# reg_MIC29752.net
KiCad netlist of a schematic drawn in EAGLE
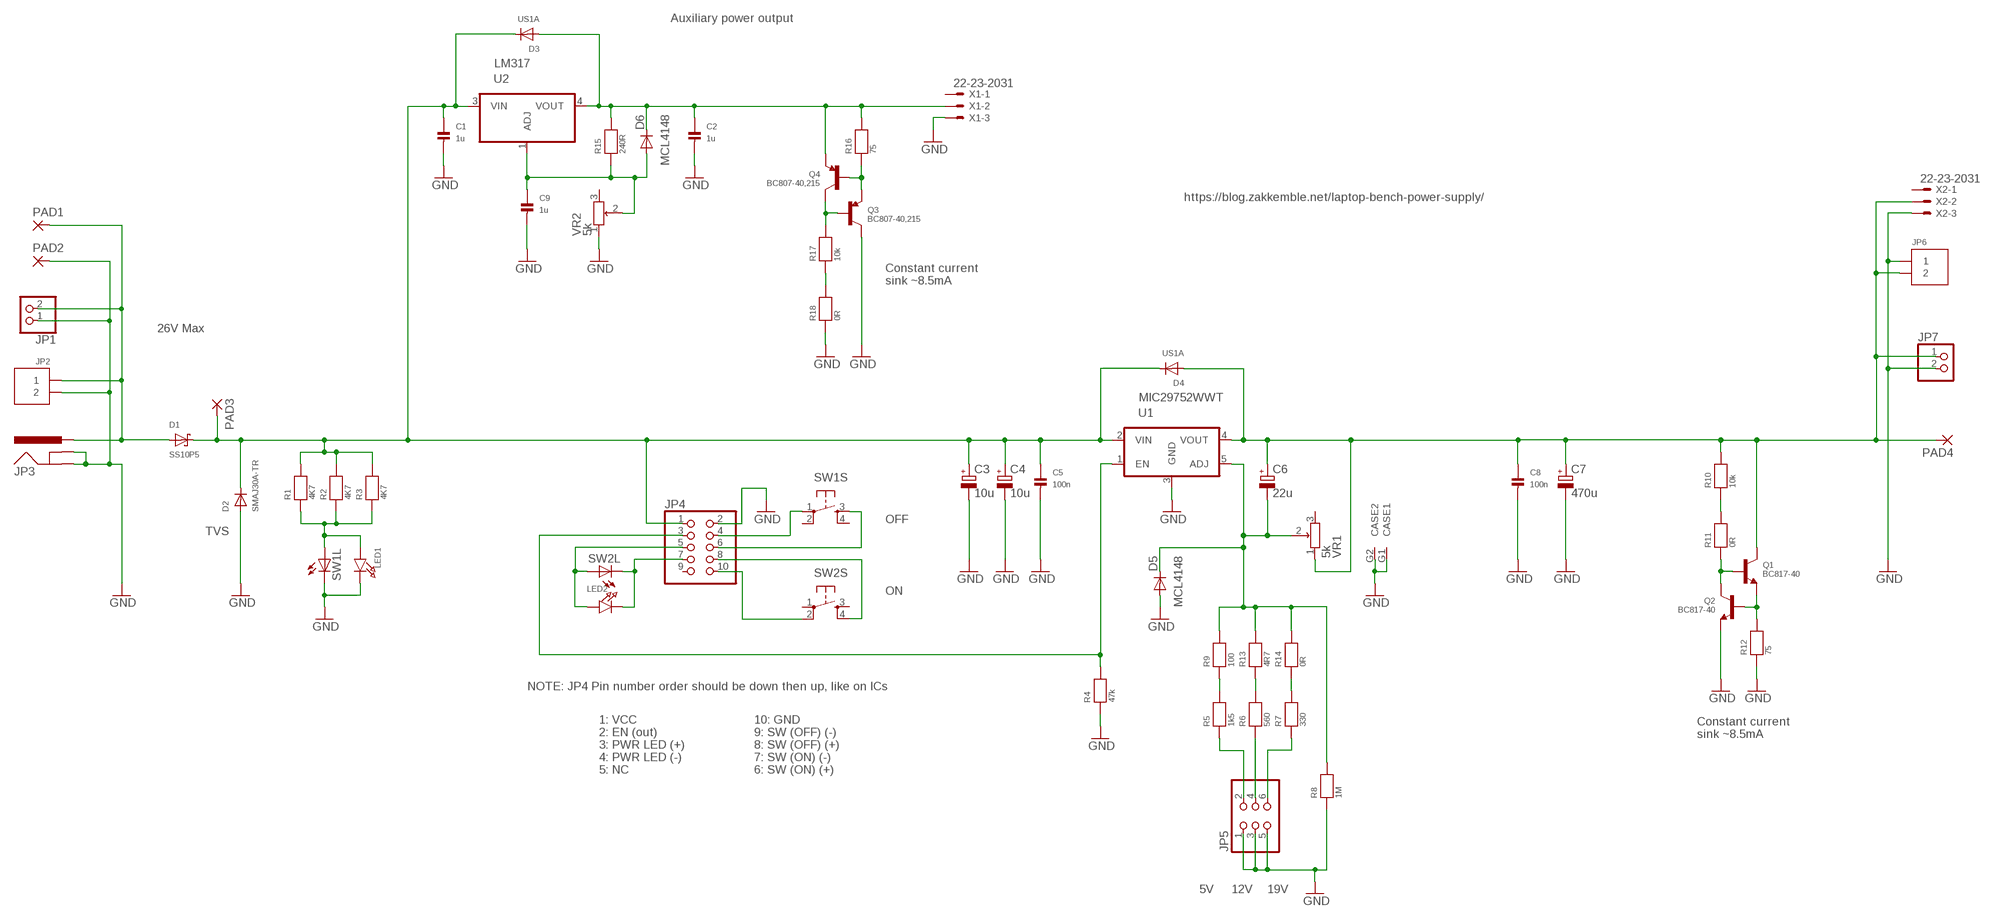
[diagram p0: schematic, sheet 1]

(export (version "E")
  (design (tool "Eeschema 10.0.6"))
  (components
    (comp (ref "C1")
      (value "1u")
      (footprint "eagle-import:0805_NO_OUTLINE")
      (libsource (lib "eagle-import") (part "zak_CAP_CERAMIC0805"))
    )
    (comp (ref "C2")
      (value "1u")
      (footprint "eagle-import:0805_NO_OUTLINE")
      (libsource (lib "eagle-import") (part "zak_CAP_CERAMIC0805"))
    )
    (comp (ref "C3")
      (value "10u")
      (footprint "eagle-import:E2-5")
      (libsource (lib "eagle-import") (part "CPOL-EUE2-5"))
    )
    (comp (ref "C4")
      (value "10u")
      (footprint "eagle-import:E2-5")
      (libsource (lib "eagle-import") (part "CPOL-EUE2-5"))
    )
    (comp (ref "C5")
      (value "100n")
      (footprint "eagle-import:_0603MP")
      (libsource (lib "eagle-import") (part "CAP_CERAMIC_0603MP"))
    )
    (comp (ref "C6")
      (value "22u")
      (footprint "eagle-import:E2-4")
      (libsource (lib "eagle-import") (part "CPOL-EUE2-4"))
    )
    (comp (ref "C7")
      (value "470u")
      (footprint "eagle-import:E5-10,5")
      (libsource (lib "eagle-import") (part "CPOL-EUE5-10.5"))
    )
    (comp (ref "C8")
      (value "100n")
      (footprint "eagle-import:_0603MP")
      (libsource (lib "eagle-import") (part "CAP_CERAMIC_0603MP"))
    )
    (comp (ref "C9")
      (value "1u")
      (footprint "eagle-import:0805_NO_OUTLINE")
      (libsource (lib "eagle-import") (part "zak_CAP_CERAMIC0805"))
    )
    (comp (ref "D1")
      (value "SS10P5")
      (footprint "eagle-import:TO-277A")
      (libsource (lib "eagle-import") (part "DIODE-SCHOTTKYTO-277A"))
    )
    (comp (ref "D2")
      (value "SMAJ30A-TR")
      (footprint "eagle-import:SMADIODE")
      (libsource (lib "eagle-import") (part "DIODESMA"))
    )
    (comp (ref "D3")
      (value "US1A")
      (footprint "eagle-import:SMADIODE")
      (libsource (lib "eagle-import") (part "DIODESMA"))
    )
    (comp (ref "D4")
      (value "US1A")
      (footprint "eagle-import:SMADIODE")
      (libsource (lib "eagle-import") (part "DIODESMA"))
    )
    (comp (ref "D5")
      (value "MCL4148")
      (footprint "eagle-import:MICROMELF-R")
      (libsource (lib "eagle-import") (part "DIODE-MICROMELF-R"))
    )
    (comp (ref "D6")
      (value "MCL4148")
      (footprint "eagle-import:MICROMELF-R")
      (libsource (lib "eagle-import") (part "DIODE-MICROMELF-R"))
    )
    (comp (ref "JP1")
      (value "PINHD-1X2")
      (footprint "eagle-import:1X02")
      (libsource (lib "eagle-import") (part "PINHD-1X2"))
    )
    (comp (ref "JP2")
      (value "TERM_BLOCK_2WAY")
      (footprint "eagle-import:TERM_2WAY")
      (libsource (lib "eagle-import") (part "TERM_BLOCK_2WAY"))
    )
    (comp (ref "JP3")
      (value "POWER_JACKPTH_HIGHCURRENT")
      (footprint "eagle-import:POWER_JACK_PTH_HIGHCURRENT")
      (libsource (lib "eagle-import") (part "POWER_JACKPTH_HIGHCURRENT"))
    )
    (comp (ref "JP4")
      (value "PINHD-2X5")
      (footprint "eagle-import:2X05")
      (libsource (lib "eagle-import") (part "PINHD-2X5"))
    )
    (comp (ref "JP5")
      (value "PINHD-2X3")
      (footprint "eagle-import:2X03")
      (libsource (lib "eagle-import") (part "PINHD-2X3"))
    )
    (comp (ref "JP6")
      (value "TERM_BLOCK_2WAY")
      (footprint "eagle-import:TERM_2WAY")
      (libsource (lib "eagle-import") (part "TERM_BLOCK_2WAY"))
    )
    (comp (ref "JP7")
      (value "PINHD-1X2")
      (footprint "eagle-import:1X02")
      (libsource (lib "eagle-import") (part "PINHD-1X2"))
    )
    (comp (ref "LED1")
      (value "LED0603_NOOUTLINE")
      (footprint "eagle-import:CHIPLED_0603_NOOUTLINE")
      (libsource (lib "eagle-import") (part "LED0603_NOOUTLINE"))
    )
    (comp (ref "LED2")
      (value "LED0603_NOOUTLINE")
      (footprint "eagle-import:CHIPLED_0603_NOOUTLINE")
      (libsource (lib "eagle-import") (part "LED0603_NOOUTLINE"))
    )
    (comp (ref "PAD1")
      (value "WIREPAD-3.81,2SCREW-3MM")
      (footprint "eagle-import:SCREWPAD-3MM")
      (libsource (lib "eagle-import") (part "WIREPAD-3.81,2SCREW-3MM"))
    )
    (comp (ref "PAD2")
      (value "WIREPAD-3.81,2SCREW-3MM")
      (footprint "eagle-import:SCREWPAD-3MM")
      (libsource (lib "eagle-import") (part "WIREPAD-3.81,2SCREW-3MM"))
    )
    (comp (ref "PAD3")
      (value "WIREPAD-3.81,2SCREW-3MM")
      (footprint "eagle-import:SCREWPAD-3MM")
      (libsource (lib "eagle-import") (part "WIREPAD-3.81,2SCREW-3MM"))
    )
    (comp (ref "PAD4")
      (value "WIREPAD-3.81,2SCREW-3MM")
      (footprint "eagle-import:SCREWPAD-3MM")
      (libsource (lib "eagle-import") (part "WIREPAD-3.81,2SCREW-3MM"))
    )
    (comp (ref "Q1")
      (value "BC817-40")
      (footprint "eagle-import:SOT23-W")
      (libsource (lib "eagle-import") (part "TRANSISTOR_NPNWAVE"))
    )
    (comp (ref "Q2")
      (value "BC817-40")
      (footprint "eagle-import:SOT23-WIDE")
      (libsource (lib "eagle-import") (part "TRANSISTOR_NPNWIDE"))
    )
    (comp (ref "Q3")
      (value "BC807-40,215")
      (footprint "eagle-import:SOT23-W")
      (libsource (lib "eagle-import") (part "TRANSISTOR_PNPSOT23-WAVE"))
    )
    (comp (ref "Q4")
      (value "BC807-40,215")
      (footprint "eagle-import:SOT23-WIDE")
      (libsource (lib "eagle-import") (part "TRANSISTOR_PNPWIDE"))
    )
    (comp (ref "R1")
      (value "4K7")
      (footprint "eagle-import:0402")
      (libsource (lib "eagle-import") (part "RESISTOR0402"))
    )
    (comp (ref "R2")
      (value "4K7")
      (footprint "eagle-import:0402")
      (libsource (lib "eagle-import") (part "RESISTOR0402"))
    )
    (comp (ref "R3")
      (value "4K7")
      (footprint "eagle-import:0402")
      (libsource (lib "eagle-import") (part "RESISTOR0402"))
    )
    (comp (ref "R4")
      (value "47k")
      (footprint "eagle-import:0402")
      (libsource (lib "eagle-import") (part "RESISTOR0402"))
    )
    (comp (ref "R5")
      (value "1k5")
      (footprint "eagle-import:0402")
      (libsource (lib "eagle-import") (part "RESISTOR0402"))
    )
    (comp (ref "R6")
      (value "560")
      (footprint "eagle-import:0402")
      (libsource (lib "eagle-import") (part "RESISTOR0402"))
    )
    (comp (ref "R7")
      (value "330")
      (footprint "eagle-import:0402")
      (libsource (lib "eagle-import") (part "RESISTOR0402"))
    )
    (comp (ref "R8")
      (value "1M")
      (footprint "eagle-import:0402")
      (libsource (lib "eagle-import") (part "RESISTOR0402"))
    )
    (comp (ref "R9")
      (value "100")
      (footprint "eagle-import:0402")
      (libsource (lib "eagle-import") (part "RESISTOR0402"))
    )
    (comp (ref "R10")
      (value "10k")
      (footprint "eagle-import:0402")
      (libsource (lib "eagle-import") (part "RESISTOR0402"))
    )
    (comp (ref "R11")
      (value "0R")
      (footprint "eagle-import:0402")
      (libsource (lib "eagle-import") (part "RESISTOR0402"))
    )
    (comp (ref "R12")
      (value "75")
      (footprint "eagle-import:0402")
      (libsource (lib "eagle-import") (part "RESISTOR0402"))
    )
    (comp (ref "R13")
      (value "4R7")
      (footprint "eagle-import:0402")
      (libsource (lib "eagle-import") (part "RESISTOR0402"))
    )
    (comp (ref "R14")
      (value "0R")
      (footprint "eagle-import:0402")
      (libsource (lib "eagle-import") (part "RESISTOR0402"))
    )
    (comp (ref "R15")
      (value "240R")
      (footprint "eagle-import:0402")
      (libsource (lib "eagle-import") (part "RESISTOR0402"))
    )
    (comp (ref "R16")
      (value "75")
      (footprint "eagle-import:0402")
      (libsource (lib "eagle-import") (part "RESISTOR0402"))
    )
    (comp (ref "R17")
      (value "10k")
      (footprint "eagle-import:0402")
      (libsource (lib "eagle-import") (part "RESISTOR0402"))
    )
    (comp (ref "R18")
      (value "0R")
      (footprint "eagle-import:0402")
      (libsource (lib "eagle-import") (part "RESISTOR0402"))
    )
    (comp (ref "SW1")
      (value "SPST_TACT_LED12MM_TH")
      (footprint "eagle-import:TACT_TH_12MM_LED")
      (libsource (lib "eagle-import") (part "SPST_TACT_LED12MM_TH"))
    )
    (comp (ref "SW2")
      (value "SPST_TACT_LED12MM_TH")
      (footprint "eagle-import:TACT_TH_12MM_LED")
      (libsource (lib "eagle-import") (part "SPST_TACT_LED12MM_TH"))
    )
    (comp (ref "U1")
      (value "MIC29752WWT")
      (footprint "eagle-import:TO247-5-REVERSE")
      (libsource (lib "eagle-import") (part "REGULATOR_3_ADJ_ENTO247-5-REVERSE"))
    )
    (comp (ref "U2")
      (value "LM317")
      (footprint "eagle-import:DPAK")
      (libsource (lib "eagle-import") (part "REGULATOR_3_ADJDPAK"))
    )
    (comp (ref "VR1")
      (value "5k")
      (footprint "eagle-import:RV09")
      (libsource (lib "eagle-import") (part "POTENTIOMETER_RV09RV09"))
    )
    (comp (ref "VR2")
      (value "5k")
      (footprint "eagle-import:TRIMPOT_BOURNS3MM")
      (libsource (lib "eagle-import") (part "POTENTIOMETERBOURNS3MM"))
    )
    (comp (ref "X1")
      (value "22-23-2031")
      (footprint "eagle-import:22-23-2031")
      (fields (field (name "MF") "MOLEX"))
      (libsource (lib "eagle-import") (part "22-23-2031"))
    )
    (comp (ref "X2")
      (value "22-23-2031")
      (footprint "eagle-import:22-23-2031")
      (fields (field (name "MF") "MOLEX"))
      (libsource (lib "eagle-import") (part "22-23-2031"))
    )
  )
  (nets
    (net (code "1") (name "GND") (class "Default")
      (node (ref "C1") (pin "2") (pinfunction "P$2_2") (pintype "passive"))
      (node (ref "C2") (pin "2") (pinfunction "P$2_2") (pintype "passive"))
      (node (ref "C3") (pin "-") (pinfunction "-_-") (pintype "passive"))
      (node (ref "C4") (pin "-") (pinfunction "-_-") (pintype "passive"))
      (node (ref "C5") (pin "2") (pinfunction "P$2_2") (pintype "passive"))
      (node (ref "C7") (pin "-") (pinfunction "-_-") (pintype "passive"))
      (node (ref "C8") (pin "2") (pinfunction "P$2_2") (pintype "passive"))
      (node (ref "C9") (pin "2") (pinfunction "P$2_2") (pintype "passive"))
      (node (ref "D2") (pin "A") (pinfunction "A_A") (pintype "passive"))
      (node (ref "D5") (pin "A") (pinfunction "A_A") (pintype "passive"))
      (node (ref "JP1") (pin "1") (pinfunction "1_1") (pintype "passive"))
      (node (ref "JP2") (pin "2") (pinfunction "2_2") (pintype "passive"))
      (node (ref "JP3") (pin "C1") (pinfunction "GNDBREAK_C1") (pintype "bidirectional"))
      (node (ref "JP3") (pin "C2") (pinfunction "GNDBREAK_C2") (pintype "bidirectional"))
      (node (ref "JP3") (pin "C3") (pinfunction "GNDBREAK_C3") (pintype "bidirectional"))
      (node (ref "JP3") (pin "C4") (pinfunction "GNDBREAK_C4") (pintype "bidirectional"))
      (node (ref "JP3") (pin "GND") (pinfunction "GND_GND") (pintype "bidirectional"))
      (node (ref "JP4") (pin "2") (pinfunction "2_2") (pintype "passive"))
      (node (ref "JP5") (pin "1") (pinfunction "1_1") (pintype "passive"))
      (node (ref "JP5") (pin "3") (pinfunction "3_3") (pintype "passive"))
      (node (ref "JP5") (pin "5") (pinfunction "5_5") (pintype "passive"))
      (node (ref "JP6") (pin "1") (pinfunction "1_1") (pintype "passive"))
      (node (ref "JP7") (pin "2") (pinfunction "2_2") (pintype "passive"))
      (node (ref "LED1") (pin "C") (pinfunction "C_C") (pintype "passive"))
      (node (ref "PAD2") (pin "1") (pinfunction "P_1") (pintype "passive"))
      (node (ref "Q2") (pin "2") (pinfunction "E_2") (pintype "passive"))
      (node (ref "Q3") (pin "3") (pinfunction "C_3") (pintype "passive"))
      (node (ref "R12") (pin "1") (pinfunction "1_1") (pintype "passive"))
      (node (ref "R18") (pin "1") (pinfunction "1_1") (pintype "passive"))
      (node (ref "R4") (pin "1") (pinfunction "1_1") (pintype "passive"))
      (node (ref "R8") (pin "1") (pinfunction "1_1") (pintype "passive"))
      (node (ref "SW1") (pin "5") (pinfunction "C_5") (pintype "passive"))
      (node (ref "U1") (pin "3") (pinfunction "GND_3") (pintype "power_in"))
      (node (ref "VR1") (pin "G1") (pinfunction "CASE1_G1") (pintype "bidirectional"))
      (node (ref "VR1") (pin "G2") (pinfunction "CASE2_G2") (pintype "bidirectional"))
      (node (ref "VR2") (pin "1") (pinfunction "1A_1") (pintype "passive"))
      (node (ref "X1") (pin "3") (pinfunction "S_3") (pintype "passive"))
      (node (ref "X2") (pin "3") (pinfunction "S_3") (pintype "passive"))
    )
    (net (code "2") (name "Net-(C1-P$1)") (class "Default")
      (node (ref "C1") (pin "1") (pinfunction "P$1_1") (pintype "passive"))
      (node (ref "C3") (pin "+") (pinfunction "+_+") (pintype "passive"))
      (node (ref "C4") (pin "+") (pinfunction "+_+") (pintype "passive"))
      (node (ref "C5") (pin "1") (pinfunction "P$1_1") (pintype "passive"))
      (node (ref "D1") (pin "K") (pinfunction "C_K") (pintype "passive"))
      (node (ref "D2") (pin "C") (pinfunction "C_C") (pintype "passive"))
      (node (ref "D3") (pin "C") (pinfunction "C_C") (pintype "passive"))
      (node (ref "D4") (pin "C") (pinfunction "C_C") (pintype "passive"))
      (node (ref "JP4") (pin "1") (pinfunction "1_1") (pintype "passive"))
      (node (ref "PAD3") (pin "1") (pinfunction "P_1") (pintype "passive"))
      (node (ref "R1") (pin "2") (pinfunction "2_2") (pintype "passive"))
      (node (ref "R2") (pin "2") (pinfunction "2_2") (pintype "passive"))
      (node (ref "R3") (pin "2") (pinfunction "2_2") (pintype "passive"))
      (node (ref "U1") (pin "2") (pinfunction "VIN_2") (pintype "power_in"))
      (node (ref "U2") (pin "3") (pinfunction "VIN_3") (pintype "power_in"))
    )
    (net (code "3") (name "Net-(C2-P$1)") (class "Default")
      (node (ref "C2") (pin "1") (pinfunction "P$1_1") (pintype "passive"))
      (node (ref "D3") (pin "A") (pinfunction "A_A") (pintype "passive"))
      (node (ref "D6") (pin "C") (pinfunction "C_C") (pintype "passive"))
      (node (ref "Q4") (pin "2") (pinfunction "E_2") (pintype "passive"))
      (node (ref "R15") (pin "2") (pinfunction "2_2") (pintype "passive"))
      (node (ref "R16") (pin "2") (pinfunction "2_2") (pintype "passive"))
      (node (ref "U2") (pin "4") (pinfunction "VOUT_4") (pintype "output"))
      (node (ref "X1") (pin "2") (pinfunction "S_2") (pintype "passive"))
    )
    (net (code "4") (name "Net-(C8-P$1)") (class "Default")
      (node (ref "C6") (pin "+") (pinfunction "+_+") (pintype "passive"))
      (node (ref "C7") (pin "+") (pinfunction "+_+") (pintype "passive"))
      (node (ref "C8") (pin "1") (pinfunction "P$1_1") (pintype "passive"))
      (node (ref "D4") (pin "A") (pinfunction "A_A") (pintype "passive"))
      (node (ref "JP6") (pin "2") (pinfunction "2_2") (pintype "passive"))
      (node (ref "JP7") (pin "1") (pinfunction "1_1") (pintype "passive"))
      (node (ref "PAD4") (pin "1") (pinfunction "P_1") (pintype "passive"))
      (node (ref "Q1") (pin "3") (pinfunction "C_3") (pintype "passive"))
      (node (ref "R10") (pin "2") (pinfunction "2_2") (pintype "passive"))
      (node (ref "U1") (pin "4") (pinfunction "VOUT_4") (pintype "output"))
      (node (ref "VR1") (pin "1") (pinfunction "1A_1") (pintype "passive"))
      (node (ref "X2") (pin "2") (pinfunction "S_2") (pintype "passive"))
    )
    (net (code "5") (name "Net-(C9-P$1)") (class "Default")
      (node (ref "C9") (pin "1") (pinfunction "P$1_1") (pintype "passive"))
      (node (ref "D6") (pin "A") (pinfunction "A_A") (pintype "passive"))
      (node (ref "R15") (pin "1") (pinfunction "1_1") (pintype "passive"))
      (node (ref "U2") (pin "1") (pinfunction "ADJ_1") (pintype "passive"))
      (node (ref "VR2") (pin "2") (pinfunction "1S_2") (pintype "passive"))
    )
    (net (code "6") (name "Net-(JP5-Pad2)") (class "Default")
      (node (ref "JP5") (pin "2") (pinfunction "2_2") (pintype "passive"))
      (node (ref "R5") (pin "1") (pinfunction "1_1") (pintype "passive"))
    )
    (net (code "7") (name "Net-(JP5-Pad4)") (class "Default")
      (node (ref "JP5") (pin "4") (pinfunction "4_4") (pintype "passive"))
      (node (ref "R6") (pin "1") (pinfunction "1_1") (pintype "passive"))
    )
    (net (code "8") (name "Net-(JP5-Pad6)") (class "Default")
      (node (ref "JP5") (pin "6") (pinfunction "6_6") (pintype "passive"))
      (node (ref "R7") (pin "1") (pinfunction "1_1") (pintype "passive"))
    )
    (net (code "9") (name "Net-(PAD1-P)") (class "Default")
      (node (ref "D1") (pin "1") (pinfunction "A_1") (pintype "passive"))
      (node (ref "D1") (pin "2") (pinfunction "A_2") (pintype "passive"))
      (node (ref "JP1") (pin "2") (pinfunction "2_2") (pintype "passive"))
      (node (ref "JP2") (pin "1") (pinfunction "1_1") (pintype "passive"))
      (node (ref "JP3") (pin "PWR") (pinfunction "PWR_PWR") (pintype "bidirectional"))
      (node (ref "PAD1") (pin "1") (pinfunction "P_1") (pintype "passive"))
    )
    (net (code "10") (name "Net-(Q1-B)") (class "Default")
      (node (ref "Q1") (pin "1") (pinfunction "B_1") (pintype "passive"))
      (node (ref "Q2") (pin "3") (pinfunction "C_3") (pintype "passive"))
      (node (ref "R11") (pin "1") (pinfunction "1_1") (pintype "passive"))
    )
    (net (code "11") (name "Net-(Q1-E)") (class "Default")
      (node (ref "Q1") (pin "2") (pinfunction "E_2") (pintype "passive"))
      (node (ref "Q2") (pin "1") (pinfunction "B_1") (pintype "passive"))
      (node (ref "R12") (pin "2") (pinfunction "2_2") (pintype "passive"))
    )
    (net (code "12") (name "Net-(Q3-B)") (class "Default")
      (node (ref "Q3") (pin "1") (pinfunction "B_1") (pintype "passive"))
      (node (ref "Q4") (pin "3") (pinfunction "C_3") (pintype "passive"))
      (node (ref "R17") (pin "2") (pinfunction "2_2") (pintype "passive"))
    )
    (net (code "13") (name "Net-(Q3-E)") (class "Default")
      (node (ref "Q3") (pin "2") (pinfunction "E_2") (pintype "passive"))
      (node (ref "Q4") (pin "1") (pinfunction "B_1") (pintype "passive"))
      (node (ref "R16") (pin "1") (pinfunction "1_1") (pintype "passive"))
    )
    (net (code "14") (name "Net-(R5-Pad2)") (class "Default")
      (node (ref "R5") (pin "2") (pinfunction "2_2") (pintype "passive"))
      (node (ref "R9") (pin "1") (pinfunction "1_1") (pintype "passive"))
    )
    (net (code "15") (name "Net-(R10-Pad1)") (class "Default")
      (node (ref "R10") (pin "1") (pinfunction "1_1") (pintype "passive"))
      (node (ref "R11") (pin "2") (pinfunction "2_2") (pintype "passive"))
    )
    (net (code "16") (name "Net-(R13-Pad1)") (class "Default")
      (node (ref "R13") (pin "1") (pinfunction "1_1") (pintype "passive"))
      (node (ref "R6") (pin "2") (pinfunction "2_2") (pintype "passive"))
    )
    (net (code "17") (name "Net-(R14-Pad1)") (class "Default")
      (node (ref "R14") (pin "1") (pinfunction "1_1") (pintype "passive"))
      (node (ref "R7") (pin "2") (pinfunction "2_2") (pintype "passive"))
    )
    (net (code "18") (name "Net-(R17-Pad1)") (class "Default")
      (node (ref "R17") (pin "1") (pinfunction "1_1") (pintype "passive"))
      (node (ref "R18") (pin "2") (pinfunction "2_2") (pintype "passive"))
    )
    (net (code "19") (name "Net-(SW1A-A)") (class "Default")
      (node (ref "LED1") (pin "A") (pinfunction "A_A") (pintype "passive"))
      (node (ref "R1") (pin "1") (pinfunction "1_1") (pintype "passive"))
      (node (ref "R2") (pin "1") (pinfunction "1_1") (pintype "passive"))
      (node (ref "R3") (pin "1") (pinfunction "1_1") (pintype "passive"))
      (node (ref "SW1") (pin "6") (pinfunction "A_6") (pintype "passive"))
    )
    (net (code "20") (name "Net-(SW1B-P)") (class "Default")
      (node (ref "JP4") (pin "4") (pinfunction "4_4") (pintype "passive"))
      (node (ref "SW1") (pin "1") (pinfunction "P_1") (pintype "passive"))
    )
    (net (code "21") (name "Net-(SW1B-S)") (class "Default")
      (node (ref "JP4") (pin "6") (pinfunction "6_6") (pintype "passive"))
      (node (ref "SW1") (pin "3") (pinfunction "S_3") (pintype "passive"))
    )
    (net (code "22") (name "Net-(SW2A-A)") (class "Default")
      (node (ref "JP4") (pin "5") (pinfunction "5_5") (pintype "passive"))
      (node (ref "LED2") (pin "A") (pinfunction "A_A") (pintype "passive"))
      (node (ref "SW2") (pin "6") (pinfunction "A_6") (pintype "passive"))
    )
    (net (code "23") (name "Net-(SW2A-C)") (class "Default")
      (node (ref "JP4") (pin "7") (pinfunction "7_7") (pintype "passive"))
      (node (ref "LED2") (pin "C") (pinfunction "C_C") (pintype "passive"))
      (node (ref "SW2") (pin "5") (pinfunction "C_5") (pintype "passive"))
    )
    (net (code "24") (name "Net-(SW2B-P1)") (class "Default")
      (node (ref "JP4") (pin "10") (pinfunction "10_10") (pintype "passive"))
      (node (ref "SW2") (pin "2") (pinfunction "P1_2") (pintype "passive"))
    )
    (net (code "25") (name "Net-(SW2B-S1)") (class "Default")
      (node (ref "JP4") (pin "8") (pinfunction "8_8") (pintype "passive"))
      (node (ref "SW2") (pin "4") (pinfunction "S1_4") (pintype "passive"))
    )
    (net (code "26") (name "Net-(U1-ADJ)") (class "Default")
      (node (ref "C6") (pin "-") (pinfunction "-_-") (pintype "passive"))
      (node (ref "D5") (pin "C") (pinfunction "C_C") (pintype "passive"))
      (node (ref "R13") (pin "2") (pinfunction "2_2") (pintype "passive"))
      (node (ref "R14") (pin "2") (pinfunction "2_2") (pintype "passive"))
      (node (ref "R8") (pin "2") (pinfunction "2_2") (pintype "passive"))
      (node (ref "R9") (pin "2") (pinfunction "2_2") (pintype "passive"))
      (node (ref "U1") (pin "5") (pinfunction "ADJ_5") (pintype "passive"))
      (node (ref "VR1") (pin "2") (pinfunction "1S_2") (pintype "passive"))
    )
    (net (code "27") (name "Net-(U1-EN)") (class "Default")
      (node (ref "JP4") (pin "3") (pinfunction "3_3") (pintype "passive"))
      (node (ref "R4") (pin "2") (pinfunction "2_2") (pintype "passive"))
      (node (ref "U1") (pin "1") (pinfunction "EN_1") (pintype "power_in"))
    )
    (net (code "28") (name "unconnected-(JP4-Pad9)") (class "Default")
      (node (ref "JP4") (pin "9") (pinfunction "9_9") (pintype "passive"))
    )
    (net (code "29") (name "unconnected-(SW1B-P1-Pad2)") (class "Default")
      (node (ref "SW1") (pin "2") (pinfunction "P1_2") (pintype "passive"))
    )
    (net (code "30") (name "unconnected-(SW1B-S1-Pad4)") (class "Default")
      (node (ref "SW1") (pin "4") (pinfunction "S1_4") (pintype "passive"))
    )
    (net (code "31") (name "unconnected-(SW2B-P-Pad1)") (class "Default")
      (node (ref "SW2") (pin "1") (pinfunction "P_1") (pintype "passive"))
    )
    (net (code "32") (name "unconnected-(SW2B-S-Pad3)") (class "Default")
      (node (ref "SW2") (pin "3") (pinfunction "S_3") (pintype "passive"))
    )
    (net (code "33") (name "unconnected-(VR1-1E-Pad3)") (class "Default")
      (node (ref "VR1") (pin "3") (pinfunction "1E_3") (pintype "passive"))
    )
    (net (code "34") (name "unconnected-(VR2-1E-Pad3)") (class "Default")
      (node (ref "VR2") (pin "3") (pinfunction "1E_3") (pintype "passive"))
    )
    (net (code "35") (name "unconnected-(X1A-S-Pad1)") (class "Default")
      (node (ref "X1") (pin "1") (pinfunction "S_1") (pintype "passive"))
    )
    (net (code "36") (name "unconnected-(X2A-S-Pad1)") (class "Default")
      (node (ref "X2") (pin "1") (pinfunction "S_1") (pintype "passive"))
    )
  )
)
